# sensors_and_dpg_ports.net
KiCad netlist of a schematic drawn in Altium Designer
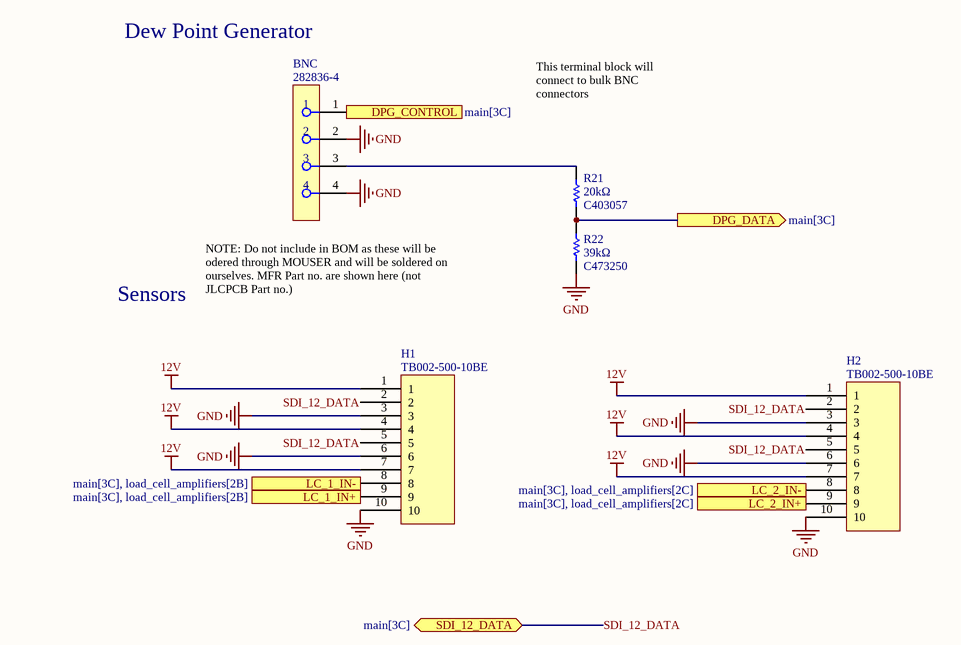
[diagram p0: sensors_and_dpg_ports.SchDoc]

(export (version "E")
  (design (tool "Eeschema 10.0.6"))
  (components
    (comp (ref "BNC")
      (value "282836-4")
      (footprint "FP-282836-4-MFG")
      (description "282836-4 Connector, Terminal Block; Wire Receptacle; 4 Pos.; 16-30 AWG; 0.197 in. CL; Sid")
      (fields (field (name "VOLTAGE") "300V") (field (name "JLCPCB PART") "jlcpcb part no."))
      (libsource (lib "Altium Content Vault") (part "282836-4"))
    )
    (comp (ref "H1")
      (value "TB002-500-10BE")
      (footprint "TB002-500-10BE")
      (description "2~24 Poles, Screw Type, Horizontal, 5.0 Pitch, 22~12 (AWG), Terminal Block Connector")
      (fields (field (name "JLCPCB PART") "jlcpcb part no."))
      (libsource (lib "James Cook University") (part "TB002-500-10BE-Symbol-1"))
    )
    (comp (ref "H2")
      (value "TB002-500-10BE")
      (footprint "TB002-500-10BE")
      (description "2~24 Poles, Screw Type, Horizontal, 5.0 Pitch, 22~12 (AWG), Terminal Block Connector")
      (fields (field (name "JLCPCB PART") "jlcpcb part no."))
      (libsource (lib "James Cook University") (part "TB002-500-10BE-Symbol-1"))
    )
    (comp (ref "R21")
      (value "ERJ-3EKF2002V")
      (footprint "RESC1608X55X30ML15T15")
      (fields
        (field (name "MANUFACTURER") "Panasonic")
        (field (name "RESISTANCE") "20kΩ")
        (field (name "JLCPCB PART") "C403057")
      )
      (libsource (lib "Altium Content Vault") (part "RES"))
    )
    (comp (ref "R22")
      (value "ERA-3AEB393V")
      (footprint "RESC1608X55X30LL20T20")
      (fields
        (field (name "MANUFACTURER") "Panasonic")
        (field (name "JLCPCB PART") "C473250")
        (field (name "RESISTANCE") "39kΩ")
      )
      (libsource (lib "Altium Content Vault") (part "RES"))
    )
  )
  (nets
    (net (code "1") (name "/DPG_CONTROL") (class "Default")
      (node (ref "BNC") (pin "1") (pinfunction "1_1") (pintype "passive"))
    )
    (net (code "2") (name "/DPG_DATA") (class "Default")
      (node (ref "R21") (pin "1") (pinfunction "1_1") (pintype "passive"))
      (node (ref "R22") (pin "2") (pinfunction "2_2") (pintype "passive"))
    )
    (net (code "3") (name "/LC_1_IN+") (class "Default")
      (node (ref "H1") (pin "9") (pinfunction "9_9") (pintype "passive"))
    )
    (net (code "4") (name "/LC_1_IN-") (class "Default")
      (node (ref "H1") (pin "8") (pinfunction "8_8") (pintype "passive"))
    )
    (net (code "5") (name "/LC_2_IN+") (class "Default")
      (node (ref "H2") (pin "9") (pinfunction "9_9") (pintype "passive"))
    )
    (net (code "6") (name "/LC_2_IN-") (class "Default")
      (node (ref "H2") (pin "8") (pinfunction "8_8") (pintype "passive"))
    )
    (net (code "7") (name "/SDI_12_DATA") (class "Default")
      (node (ref "H1") (pin "2") (pinfunction "2_2") (pintype "passive"))
      (node (ref "H1") (pin "5") (pinfunction "5_5") (pintype "passive"))
      (node (ref "H2") (pin "2") (pinfunction "2_2") (pintype "passive"))
      (node (ref "H2") (pin "5") (pinfunction "5_5") (pintype "passive"))
    )
    (net (code "8") (name "12V") (class "Default")
      (node (ref "H1") (pin "1") (pinfunction "1_1") (pintype "passive"))
      (node (ref "H1") (pin "4") (pinfunction "4_4") (pintype "passive"))
      (node (ref "H1") (pin "7") (pinfunction "7_7") (pintype "passive"))
      (node (ref "H2") (pin "1") (pinfunction "1_1") (pintype "passive"))
      (node (ref "H2") (pin "4") (pinfunction "4_4") (pintype "passive"))
      (node (ref "H2") (pin "7") (pinfunction "7_7") (pintype "passive"))
    )
    (net (code "9") (name "GND") (class "Default")
      (node (ref "BNC") (pin "2") (pinfunction "2_2") (pintype "passive"))
      (node (ref "BNC") (pin "4") (pinfunction "4_4") (pintype "passive"))
      (node (ref "H1") (pin "10") (pinfunction "10_10") (pintype "passive"))
      (node (ref "H1") (pin "3") (pinfunction "3_3") (pintype "passive"))
      (node (ref "H1") (pin "6") (pinfunction "6_6") (pintype "passive"))
      (node (ref "H2") (pin "10") (pinfunction "10_10") (pintype "passive"))
      (node (ref "H2") (pin "3") (pinfunction "3_3") (pintype "passive"))
      (node (ref "H2") (pin "6") (pinfunction "6_6") (pintype "passive"))
      (node (ref "R22") (pin "1") (pinfunction "1_1") (pintype "passive"))
    )
    (net (code "10") (name "Net-(BNC-Pad3)") (class "Default")
      (node (ref "BNC") (pin "3") (pinfunction "3_3") (pintype "passive"))
      (node (ref "R21") (pin "2") (pinfunction "2_2") (pintype "passive"))
    )
  )
)
